# Relays.net
KiCad netlist of a schematic drawn in Altium Designer
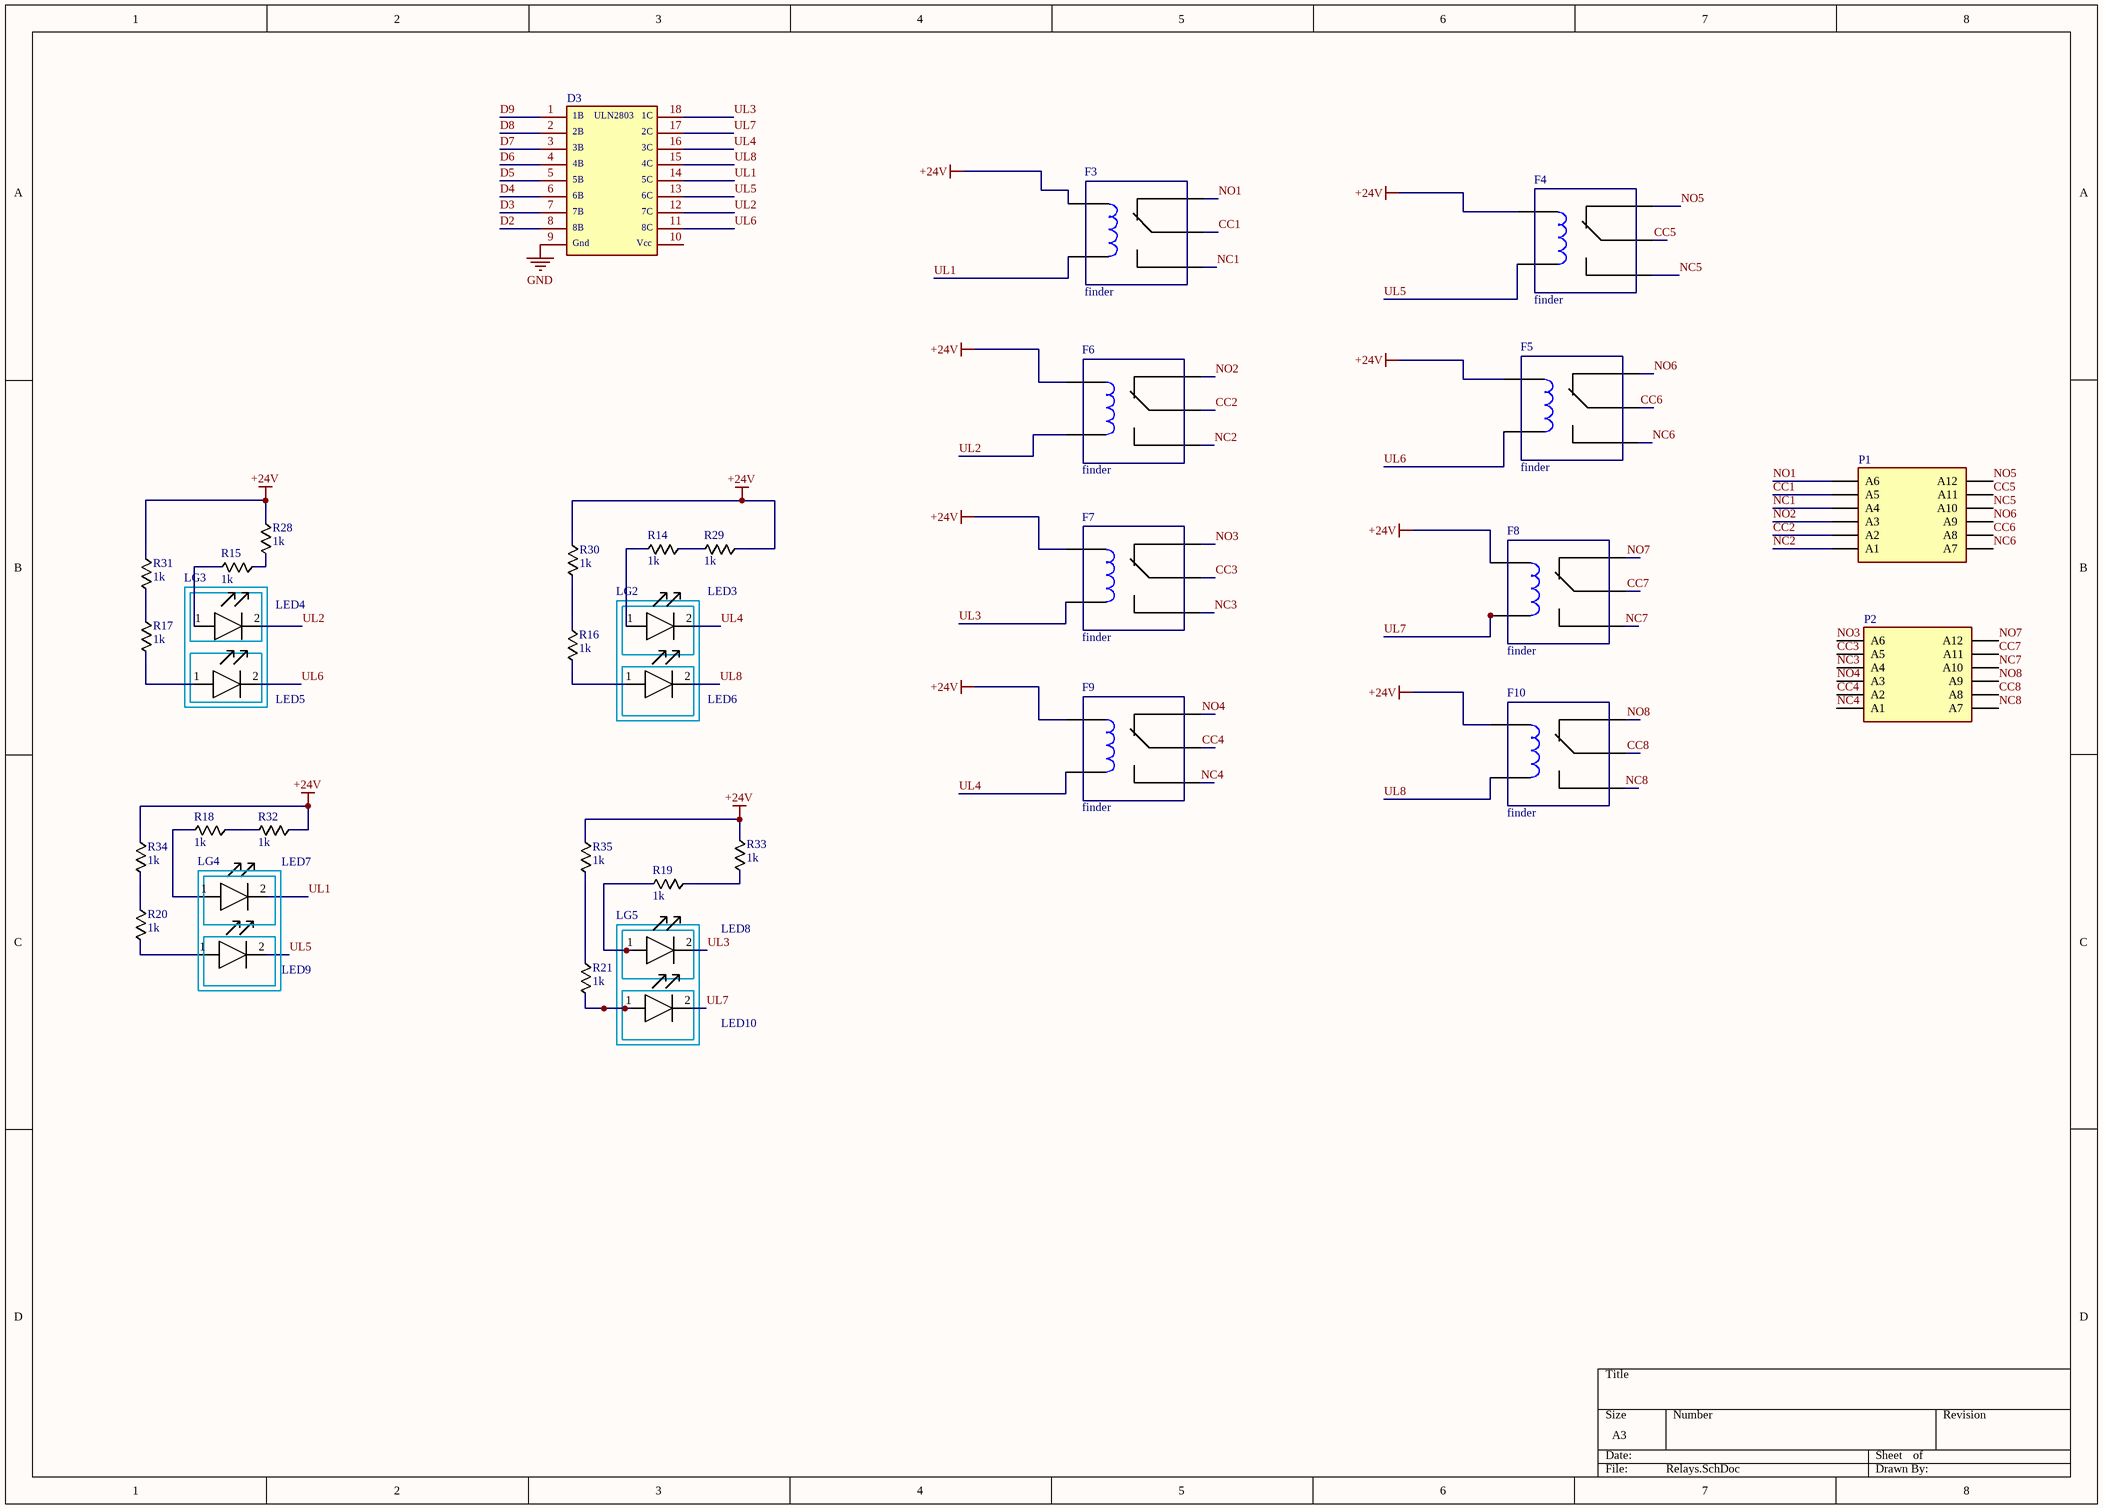
[diagram p0: Relays.SchDoc]

(export (version "E")
  (design (tool "Eeschema 10.0.6"))
  (components
    (comp (ref "D3")
      (value "~")
      (footprint "SOIC 18")
      (fields (field (name "PART NUMBER") "ULN2803ADWR"))
      (libsource (lib "kontr") (part "ULN2803 Darlington_1"))
    )
    (comp (ref "F3")
      (value "finder")
      (footprint "413190240010")
      (fields (field (name "PART NUMBER") "G2RL124DC"))
      (libsource (lib "kontr") (part "finder"))
    )
    (comp (ref "F4")
      (value "finder")
      (footprint "413190240010")
      (description "G2RL124DC")
      (libsource (lib "kontr") (part "finder"))
    )
    (comp (ref "F5")
      (value "finder")
      (footprint "413190240010")
      (description "G2RL124DC")
      (libsource (lib "kontr") (part "finder"))
    )
    (comp (ref "F6")
      (value "finder")
      (footprint "413190240010")
      (description "G2RL124DC")
      (libsource (lib "kontr") (part "finder"))
    )
    (comp (ref "F7")
      (value "finder")
      (footprint "413190240010")
      (description "G2RL124DC")
      (libsource (lib "kontr") (part "finder"))
    )
    (comp (ref "F8")
      (value "finder")
      (footprint "413190240010")
      (description "G2RL124DC")
      (libsource (lib "kontr") (part "finder"))
    )
    (comp (ref "F9")
      (value "finder")
      (footprint "413190240010")
      (description "G2RL124DC")
      (libsource (lib "kontr") (part "finder"))
    )
    (comp (ref "F10")
      (value "finder")
      (footprint "413190240010")
      (description "G2RL124DC")
      (libsource (lib "kontr") (part "finder"))
    )
    (comp (ref "LED3")
      (value "~")
      (footprint "0603 - LED")
      (fields (field (name "PART NUMBER") "KP-1608SGC"))
      (libsource (lib "МЦТР.00010572.00.001") (part "LED 0603"))
    )
    (comp (ref "LED4")
      (value "~")
      (footprint "0603 - LED")
      (fields (field (name "PART NUMBER") "KP-1608SGC"))
      (libsource (lib "МЦТР.00010572.00.001") (part "LED 0603"))
    )
    (comp (ref "LED5")
      (value "~")
      (footprint "0603 - LED")
      (fields (field (name "PART NUMBER") "KP-1608SGC"))
      (libsource (lib "МЦТР.00010572.00.001") (part "LED 0603"))
    )
    (comp (ref "LED6")
      (value "~")
      (footprint "0603 - LED")
      (fields (field (name "PART NUMBER") "KP-1608SGC"))
      (libsource (lib "МЦТР.00010572.00.001") (part "LED 0603"))
    )
    (comp (ref "LED7")
      (value "~")
      (footprint "0603 - LED")
      (fields (field (name "PART NUMBER") "KP-1608SGC"))
      (libsource (lib "МЦТР.00010572.00.001") (part "LED 0603"))
    )
    (comp (ref "LED8")
      (value "~")
      (footprint "0603 - LED")
      (fields (field (name "PART NUMBER") "KP-1608SGC"))
      (libsource (lib "МЦТР.00010572.00.001") (part "LED 0603"))
    )
    (comp (ref "LED9")
      (value "~")
      (footprint "0603 - LED")
      (fields (field (name "PART NUMBER") "KP-1608SGC"))
      (libsource (lib "МЦТР.00010572.00.001") (part "LED 0603"))
    )
    (comp (ref "LED10")
      (value "~")
      (footprint "0603 - LED")
      (fields (field (name "PART NUMBER") "KP-1608SGC"))
      (libsource (lib "МЦТР.00010572.00.001") (part "LED 0603"))
    )
    (comp (ref "LG2")
      (value "~")
      (footprint "LED SMD DayLight")
      (fields (field (name "PART NUMBER") "5151094F"))
      (libsource (lib "МЦТР.00010572.00.001") (part "Light Guide 2"))
    )
    (comp (ref "LG3")
      (value "~")
      (footprint "LED SMD DayLight")
      (fields (field (name "PART NUMBER") "5151094F"))
      (libsource (lib "МЦТР.00010572.00.001") (part "Light Guide 2"))
    )
    (comp (ref "LG4")
      (value "~")
      (footprint "LED SMD DayLight")
      (fields (field (name "PART NUMBER") "5151094F"))
      (libsource (lib "МЦТР.00010572.00.001") (part "Light Guide 2"))
    )
    (comp (ref "LG5")
      (value "~")
      (footprint "LED SMD DayLight")
      (fields (field (name "PART NUMBER") "5151094F"))
      (libsource (lib "МЦТР.00010572.00.001") (part "Light Guide 2"))
    )
    (comp (ref "P1")
      (value "~")
      (footprint "LDO_lib:mcd 1,5/6-G1-3.81")
      (fields (field (name "PART NUMBER") "MCD 1.5/6 Phoenix") (field (name "PUBLISHER") "Altium Limited"))
      (libsource (lib "kontr") (part "MCD 1.5/6 Phoenix"))
    )
    (comp (ref "P2")
      (value "~")
      (footprint "LDO_lib:mcd 1,5/6-G1-3.81")
      (fields (field (name "PART NUMBER") "MCD 1.5/6 Phoenix") (field (name "PUBLISHER") "Altium Limited"))
      (libsource (lib "kontr") (part "MCD 1.5/6 Phoenix"))
    )
    (comp (ref "R14")
      (value "1k")
      (footprint "0603_Res")
      (fields (field (name "PART NUMBER") "RC0603FR-071KL"))
      (libsource (lib "kontr") (part "Resistor 0805"))
    )
    (comp (ref "R15")
      (value "1k")
      (footprint "0603_Res")
      (fields (field (name "PART NUMBER") "RC0603FR-071KL"))
      (libsource (lib "kontr") (part "Resistor 0805"))
    )
    (comp (ref "R16")
      (value "1k")
      (footprint "0603_Res")
      (fields (field (name "PART NUMBER") "RC0603FR-071KL"))
      (libsource (lib "kontr") (part "Resistor 0805"))
    )
    (comp (ref "R17")
      (value "1k")
      (footprint "0603_Res")
      (fields (field (name "PART NUMBER") "RC0603FR-071KL"))
      (libsource (lib "kontr") (part "Resistor 0805"))
    )
    (comp (ref "R18")
      (value "1k")
      (footprint "0603_Res")
      (fields (field (name "PART NUMBER") "RC0603FR-071KL"))
      (libsource (lib "kontr") (part "Resistor 0805"))
    )
    (comp (ref "R19")
      (value "1k")
      (footprint "0603_Res")
      (fields (field (name "PART NUMBER") "RC0603FR-071KL"))
      (libsource (lib "kontr") (part "Resistor 0805"))
    )
    (comp (ref "R20")
      (value "1k")
      (footprint "0603_Res")
      (fields (field (name "PART NUMBER") "RC0603FR-071KL"))
      (libsource (lib "kontr") (part "Resistor 0805"))
    )
    (comp (ref "R21")
      (value "1k")
      (footprint "0603_Res")
      (fields (field (name "PART NUMBER") "RC0603FR-071KL"))
      (libsource (lib "kontr") (part "Resistor 0805"))
    )
    (comp (ref "R28")
      (value "1k")
      (footprint "0603_Res")
      (fields (field (name "PART NUMBER") "RC0603FR-071KL"))
      (libsource (lib "kontr") (part "Resistor 0805"))
    )
    (comp (ref "R29")
      (value "1k")
      (footprint "0603_Res")
      (fields (field (name "PART NUMBER") "RC0603FR-071KL"))
      (libsource (lib "kontr") (part "Resistor 0805"))
    )
    (comp (ref "R30")
      (value "1k")
      (footprint "0603_Res")
      (fields (field (name "PART NUMBER") "RC0603FR-071KL"))
      (libsource (lib "kontr") (part "Resistor 0805"))
    )
    (comp (ref "R31")
      (value "1k")
      (footprint "0603_Res")
      (fields (field (name "PART NUMBER") "RC0603FR-071KL"))
      (libsource (lib "kontr") (part "Resistor 0805"))
    )
    (comp (ref "R32")
      (value "1k")
      (footprint "0603_Res")
      (fields (field (name "PART NUMBER") "RC0603FR-071KL"))
      (libsource (lib "kontr") (part "Resistor 0805"))
    )
    (comp (ref "R33")
      (value "1k")
      (footprint "0603_Res")
      (fields (field (name "PART NUMBER") "RC0603FR-071KL"))
      (libsource (lib "kontr") (part "Resistor 0805"))
    )
    (comp (ref "R34")
      (value "1k")
      (footprint "0603_Res")
      (fields (field (name "PART NUMBER") "RC0603FR-071KL"))
      (libsource (lib "kontr") (part "Resistor 0805"))
    )
    (comp (ref "R35")
      (value "1k")
      (footprint "0603_Res")
      (fields (field (name "PART NUMBER") "RC0603FR-071KL"))
      (libsource (lib "kontr") (part "Resistor 0805"))
    )
  )
  (nets
    (net (code "1") (name "+24V") (class "Default")
      (node (ref "F10") (pin "A2") (pinfunction "A2_A2") (pintype "passive"))
      (node (ref "F3") (pin "A2") (pinfunction "A2_A2") (pintype "passive"))
      (node (ref "F4") (pin "A2") (pinfunction "A2_A2") (pintype "passive"))
      (node (ref "F5") (pin "A2") (pinfunction "A2_A2") (pintype "passive"))
      (node (ref "F6") (pin "A2") (pinfunction "A2_A2") (pintype "passive"))
      (node (ref "F7") (pin "A2") (pinfunction "A2_A2") (pintype "passive"))
      (node (ref "F8") (pin "A2") (pinfunction "A2_A2") (pintype "passive"))
      (node (ref "F9") (pin "A2") (pinfunction "A2_A2") (pintype "passive"))
      (node (ref "R28") (pin "1") (pintype "passive"))
      (node (ref "R29") (pin "1") (pintype "passive"))
      (node (ref "R30") (pin "1") (pintype "passive"))
      (node (ref "R31") (pin "1") (pintype "passive"))
      (node (ref "R32") (pin "1") (pintype "passive"))
      (node (ref "R33") (pin "1") (pintype "passive"))
      (node (ref "R34") (pin "1") (pintype "passive"))
      (node (ref "R35") (pin "1") (pintype "passive"))
    )
    (net (code "2") (name "/CC1") (class "Default")
      (node (ref "F3") (pin "11") (pinfunction "11_11") (pintype "passive"))
      (node (ref "P1") (pin "3") (pinfunction "A5_3") (pintype "passive"))
    )
    (net (code "3") (name "/CC2") (class "Default")
      (node (ref "F6") (pin "11") (pinfunction "11_11") (pintype "passive"))
      (node (ref "P1") (pin "9") (pinfunction "A2_9") (pintype "passive"))
    )
    (net (code "4") (name "/CC3") (class "Default")
      (node (ref "F7") (pin "11") (pinfunction "11_11") (pintype "passive"))
      (node (ref "P2") (pin "3") (pinfunction "A5_3") (pintype "passive"))
    )
    (net (code "5") (name "/CC4") (class "Default")
      (node (ref "F9") (pin "11") (pinfunction "11_11") (pintype "passive"))
      (node (ref "P2") (pin "9") (pinfunction "A2_9") (pintype "passive"))
    )
    (net (code "6") (name "/CC5") (class "Default")
      (node (ref "F4") (pin "11") (pinfunction "11_11") (pintype "passive"))
      (node (ref "P1") (pin "4") (pinfunction "A11_4") (pintype "passive"))
    )
    (net (code "7") (name "/CC6") (class "Default")
      (node (ref "F5") (pin "11") (pinfunction "11_11") (pintype "passive"))
      (node (ref "P1") (pin "10") (pinfunction "A8_10") (pintype "passive"))
    )
    (net (code "8") (name "/CC7") (class "Default")
      (node (ref "F8") (pin "11") (pinfunction "11_11") (pintype "passive"))
      (node (ref "P2") (pin "4") (pinfunction "A11_4") (pintype "passive"))
    )
    (net (code "9") (name "/CC8") (class "Default")
      (node (ref "F10") (pin "11") (pinfunction "11_11") (pintype "passive"))
      (node (ref "P2") (pin "10") (pinfunction "A8_10") (pintype "passive"))
    )
    (net (code "10") (name "/D2") (class "Default")
      (node (ref "D3") (pin "8") (pinfunction "8_8") (pintype "passive"))
    )
    (net (code "11") (name "/D3") (class "Default")
      (node (ref "D3") (pin "7") (pinfunction "7_7") (pintype "passive"))
    )
    (net (code "12") (name "/D4") (class "Default")
      (node (ref "D3") (pin "6") (pinfunction "6_6") (pintype "passive"))
    )
    (net (code "13") (name "/D5") (class "Default")
      (node (ref "D3") (pin "5") (pinfunction "5_5") (pintype "passive"))
    )
    (net (code "14") (name "/D6") (class "Default")
      (node (ref "D3") (pin "4") (pinfunction "4_4") (pintype "passive"))
    )
    (net (code "15") (name "/D7") (class "Default")
      (node (ref "D3") (pin "3") (pinfunction "3_3") (pintype "passive"))
    )
    (net (code "16") (name "/D8") (class "Default")
      (node (ref "D3") (pin "2") (pinfunction "2_2") (pintype "passive"))
    )
    (net (code "17") (name "/D9") (class "Default")
      (node (ref "D3") (pin "1") (pinfunction "1_1") (pintype "passive"))
    )
    (net (code "18") (name "/NC1") (class "Default")
      (node (ref "F3") (pin "14") (pinfunction "1_14") (pintype "passive"))
      (node (ref "P1") (pin "5") (pinfunction "A4_5") (pintype "passive"))
    )
    (net (code "19") (name "/NC2") (class "Default")
      (node (ref "F6") (pin "14") (pinfunction "1_14") (pintype "passive"))
      (node (ref "P1") (pin "11") (pinfunction "A1_11") (pintype "passive"))
    )
    (net (code "20") (name "/NC3") (class "Default")
      (node (ref "F7") (pin "14") (pinfunction "1_14") (pintype "passive"))
      (node (ref "P2") (pin "5") (pinfunction "A4_5") (pintype "passive"))
    )
    (net (code "21") (name "/NC4") (class "Default")
      (node (ref "F9") (pin "14") (pinfunction "1_14") (pintype "passive"))
      (node (ref "P2") (pin "11") (pinfunction "A1_11") (pintype "passive"))
    )
    (net (code "22") (name "/NC5") (class "Default")
      (node (ref "F4") (pin "14") (pinfunction "1_14") (pintype "passive"))
      (node (ref "P1") (pin "6") (pinfunction "A10_6") (pintype "passive"))
    )
    (net (code "23") (name "/NC6") (class "Default")
      (node (ref "F5") (pin "14") (pinfunction "1_14") (pintype "passive"))
      (node (ref "P1") (pin "12") (pinfunction "A7_12") (pintype "passive"))
    )
    (net (code "24") (name "/NC7") (class "Default")
      (node (ref "F8") (pin "14") (pinfunction "1_14") (pintype "passive"))
      (node (ref "P2") (pin "6") (pinfunction "A10_6") (pintype "passive"))
    )
    (net (code "25") (name "/NC8") (class "Default")
      (node (ref "F10") (pin "14") (pinfunction "1_14") (pintype "passive"))
      (node (ref "P2") (pin "12") (pinfunction "A7_12") (pintype "passive"))
    )
    (net (code "26") (name "/NO1") (class "Default")
      (node (ref "F3") (pin "12") (pinfunction "12_12") (pintype "passive"))
      (node (ref "P1") (pin "1") (pinfunction "A6_1") (pintype "passive"))
    )
    (net (code "27") (name "/NO2") (class "Default")
      (node (ref "F6") (pin "12") (pinfunction "12_12") (pintype "passive"))
      (node (ref "P1") (pin "7") (pinfunction "A3_7") (pintype "passive"))
    )
    (net (code "28") (name "/NO3") (class "Default")
      (node (ref "F7") (pin "12") (pinfunction "12_12") (pintype "passive"))
      (node (ref "P2") (pin "1") (pinfunction "A6_1") (pintype "passive"))
    )
    (net (code "29") (name "/NO4") (class "Default")
      (node (ref "F9") (pin "12") (pinfunction "12_12") (pintype "passive"))
      (node (ref "P2") (pin "7") (pinfunction "A3_7") (pintype "passive"))
    )
    (net (code "30") (name "/NO5") (class "Default")
      (node (ref "F4") (pin "12") (pinfunction "12_12") (pintype "passive"))
      (node (ref "P1") (pin "2") (pinfunction "A12_2") (pintype "passive"))
    )
    (net (code "31") (name "/NO6") (class "Default")
      (node (ref "F5") (pin "12") (pinfunction "12_12") (pintype "passive"))
      (node (ref "P1") (pin "8") (pinfunction "A9_8") (pintype "passive"))
    )
    (net (code "32") (name "/NO7") (class "Default")
      (node (ref "F8") (pin "12") (pinfunction "12_12") (pintype "passive"))
      (node (ref "P2") (pin "2") (pinfunction "A12_2") (pintype "passive"))
    )
    (net (code "33") (name "/NO8") (class "Default")
      (node (ref "F10") (pin "12") (pinfunction "12_12") (pintype "passive"))
      (node (ref "P2") (pin "8") (pinfunction "A9_8") (pintype "passive"))
    )
    (net (code "34") (name "/UL1") (class "Default")
      (node (ref "D3") (pin "14") (pinfunction "14_14") (pintype "passive"))
      (node (ref "F3") (pin "A1") (pinfunction "A1_A1") (pintype "passive"))
      (node (ref "LED7") (pin "2") (pintype "passive"))
    )
    (net (code "35") (name "/UL2") (class "Default")
      (node (ref "D3") (pin "12") (pinfunction "12_12") (pintype "passive"))
      (node (ref "F6") (pin "A1") (pinfunction "A1_A1") (pintype "passive"))
      (node (ref "LED4") (pin "2") (pintype "passive"))
    )
    (net (code "36") (name "/UL3") (class "Default")
      (node (ref "D3") (pin "18") (pinfunction "18_18") (pintype "passive"))
      (node (ref "F7") (pin "A1") (pinfunction "A1_A1") (pintype "passive"))
      (node (ref "LED8") (pin "2") (pintype "passive"))
    )
    (net (code "37") (name "/UL4") (class "Default")
      (node (ref "D3") (pin "16") (pinfunction "16_16") (pintype "passive"))
      (node (ref "F9") (pin "A1") (pinfunction "A1_A1") (pintype "passive"))
      (node (ref "LED3") (pin "2") (pintype "passive"))
    )
    (net (code "38") (name "/UL5") (class "Default")
      (node (ref "D3") (pin "13") (pinfunction "13_13") (pintype "passive"))
      (node (ref "F4") (pin "A1") (pinfunction "A1_A1") (pintype "passive"))
      (node (ref "LED9") (pin "2") (pintype "passive"))
    )
    (net (code "39") (name "/UL6") (class "Default")
      (node (ref "D3") (pin "11") (pinfunction "11_11") (pintype "passive"))
      (node (ref "F5") (pin "A1") (pinfunction "A1_A1") (pintype "passive"))
      (node (ref "LED5") (pin "2") (pintype "passive"))
    )
    (net (code "40") (name "/UL7") (class "Default")
      (node (ref "D3") (pin "17") (pinfunction "17_17") (pintype "passive"))
      (node (ref "F8") (pin "A1") (pinfunction "A1_A1") (pintype "passive"))
      (node (ref "LED10") (pin "2") (pintype "passive"))
    )
    (net (code "41") (name "/UL8") (class "Default")
      (node (ref "D3") (pin "15") (pinfunction "15_15") (pintype "passive"))
      (node (ref "F10") (pin "A1") (pinfunction "A1_A1") (pintype "passive"))
      (node (ref "LED6") (pin "2") (pintype "passive"))
    )
    (net (code "42") (name "GND") (class "Default")
      (node (ref "D3") (pin "9") (pinfunction "9_9") (pintype "passive"))
    )
    (net (code "43") (name "Net-(LED3-Pad1)") (class "Default")
      (node (ref "LED3") (pin "1") (pintype "passive"))
      (node (ref "R14") (pin "2") (pintype "passive"))
    )
    (net (code "44") (name "Net-(LED4-Pad1)") (class "Default")
      (node (ref "LED4") (pin "1") (pintype "passive"))
      (node (ref "R15") (pin "2") (pintype "passive"))
    )
    (net (code "45") (name "Net-(LED5-Pad1)") (class "Default")
      (node (ref "LED5") (pin "1") (pintype "passive"))
      (node (ref "R17") (pin "2") (pintype "passive"))
    )
    (net (code "46") (name "Net-(LED6-Pad1)") (class "Default")
      (node (ref "LED6") (pin "1") (pintype "passive"))
      (node (ref "R16") (pin "2") (pintype "passive"))
    )
    (net (code "47") (name "Net-(LED7-Pad1)") (class "Default")
      (node (ref "LED7") (pin "1") (pintype "passive"))
      (node (ref "R18") (pin "2") (pintype "passive"))
    )
    (net (code "48") (name "Net-(LED8-Pad1)") (class "Default")
      (node (ref "LED8") (pin "1") (pintype "passive"))
      (node (ref "R19") (pin "2") (pintype "passive"))
    )
    (net (code "49") (name "Net-(LED9-Pad1)") (class "Default")
      (node (ref "LED9") (pin "1") (pintype "passive"))
      (node (ref "R20") (pin "2") (pintype "passive"))
    )
    (net (code "50") (name "Net-(LED10-Pad1)") (class "Default")
      (node (ref "LED10") (pin "1") (pintype "passive"))
      (node (ref "R21") (pin "2") (pintype "passive"))
    )
    (net (code "51") (name "Net-(R14-Pad1)") (class "Default")
      (node (ref "R14") (pin "1") (pintype "passive"))
      (node (ref "R29") (pin "2") (pintype "passive"))
    )
    (net (code "52") (name "Net-(R15-Pad1)") (class "Default")
      (node (ref "R15") (pin "1") (pintype "passive"))
      (node (ref "R28") (pin "2") (pintype "passive"))
    )
    (net (code "53") (name "Net-(R16-Pad1)") (class "Default")
      (node (ref "R16") (pin "1") (pintype "passive"))
      (node (ref "R30") (pin "2") (pintype "passive"))
    )
    (net (code "54") (name "Net-(R17-Pad1)") (class "Default")
      (node (ref "R17") (pin "1") (pintype "passive"))
      (node (ref "R31") (pin "2") (pintype "passive"))
    )
    (net (code "55") (name "Net-(R18-Pad1)") (class "Default")
      (node (ref "R18") (pin "1") (pintype "passive"))
      (node (ref "R32") (pin "2") (pintype "passive"))
    )
    (net (code "56") (name "Net-(R19-Pad1)") (class "Default")
      (node (ref "R19") (pin "1") (pintype "passive"))
      (node (ref "R33") (pin "2") (pintype "passive"))
    )
    (net (code "57") (name "Net-(R20-Pad1)") (class "Default")
      (node (ref "R20") (pin "1") (pintype "passive"))
      (node (ref "R34") (pin "2") (pintype "passive"))
    )
    (net (code "58") (name "Net-(R21-Pad1)") (class "Default")
      (node (ref "R21") (pin "1") (pintype "passive"))
      (node (ref "R35") (pin "2") (pintype "passive"))
    )
    (net (code "59") (name "unconnected-(D3-Pad10)") (class "Default")
      (node (ref "D3") (pin "10") (pinfunction "10_10") (pintype "passive"))
    )
  )
)
